# 4_classyTKL_EC_analog.net
KiCad netlist of a schematic drawn in Altium Designer
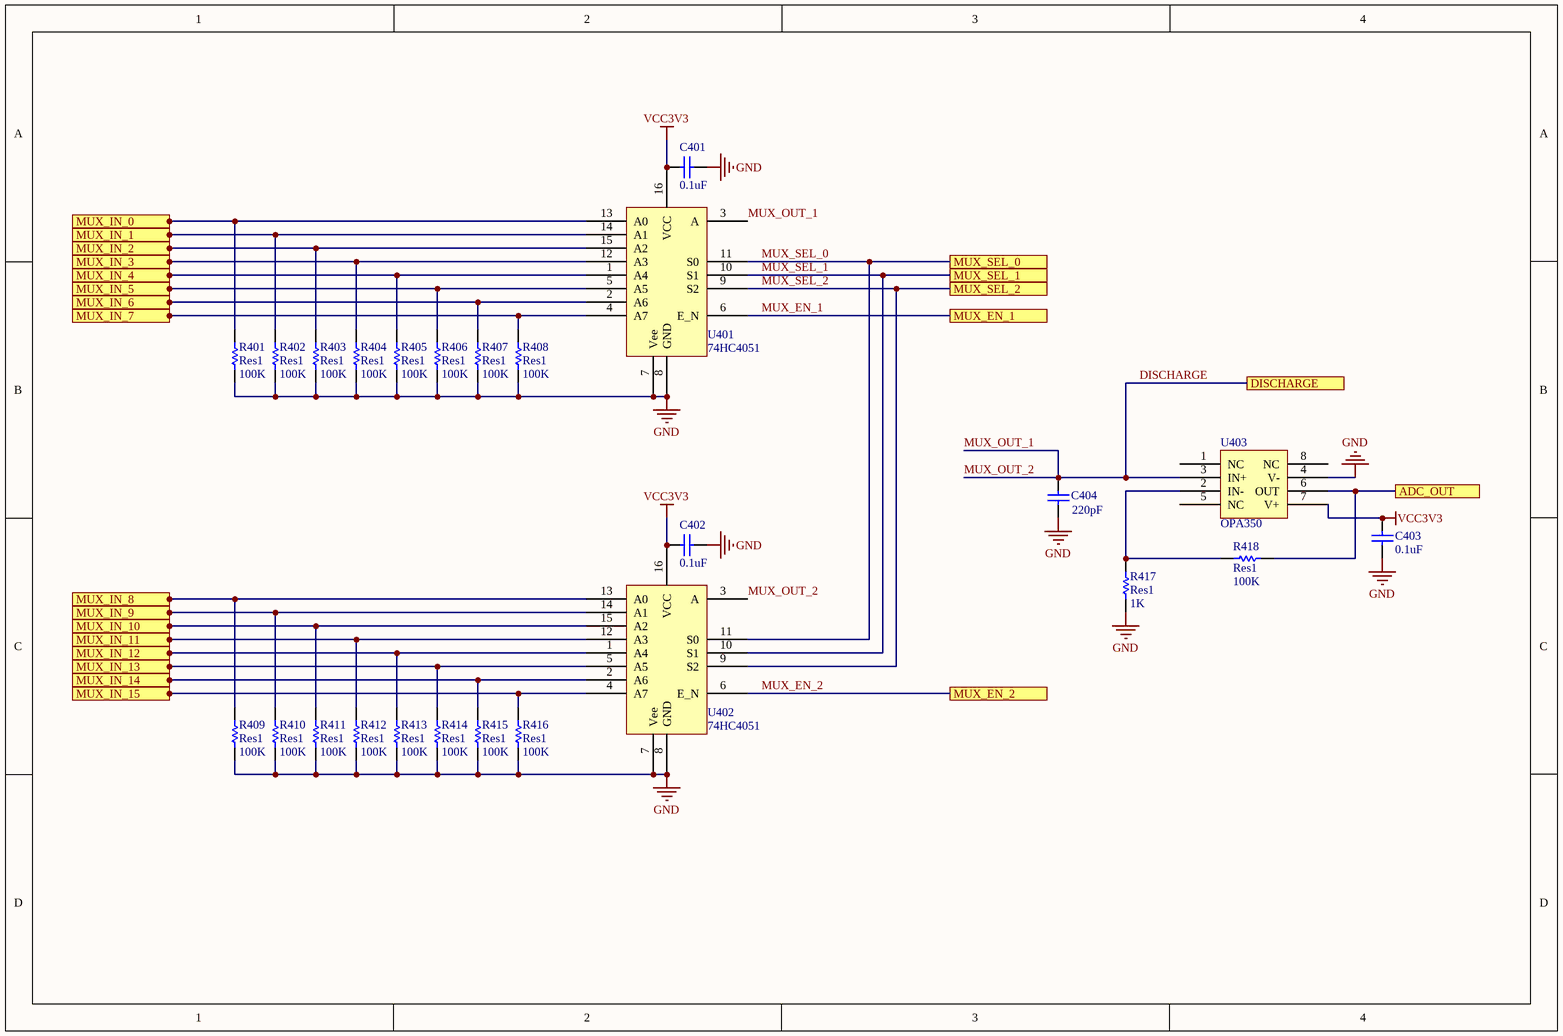
[diagram p0: 4_classyTKL_EC_analog.SchDoc]

(export (version "E")
  (design (tool "Eeschema 10.0.6"))
  (components
    (comp (ref "C401")
      (value "0.1uF")
      (footprint "C0603[1608]")
      (description "Capacitor")
      (fields (field (name "LCSC PART #") "C14663") (field (name "MRF.PART") "CC0603KRX7R9BB104"))
      (libsource (lib "Miscellaneous Devices") (part "Cap"))
    )
    (comp (ref "C402")
      (value "0.1uF")
      (footprint "C0603[1608]")
      (description "Capacitor")
      (fields (field (name "LCSC PART #") "C14663") (field (name "MRF.PART") "CC0603KRX7R9BB104"))
      (libsource (lib "Miscellaneous Devices") (part "Cap"))
    )
    (comp (ref "C403")
      (value "0.1uF")
      (footprint "C0603[1608]")
      (description "Capacitor")
      (fields (field (name "LCSC PART #") "C14663") (field (name "MRF.PART") "CC0603KRX7R9BB104"))
      (libsource (lib "Miscellaneous Devices") (part "Cap"))
    )
    (comp (ref "C404")
      (value "220pF")
      (footprint "C0603[1608]")
      (description "Capacitor")
      (fields (field (name "LCSC PART #") "C1603") (field (name "MRF.PART") "CL10B221KB8NNNC"))
      (libsource (lib "Miscellaneous Devices") (part "Cap"))
    )
    (comp (ref "R401")
      (value "Res1")
      (footprint "R0603[1608]")
      (description "Resistor")
      (fields
        (field (name "ALTIUM_VALUE") "100K")
        (field (name "LCSC PART #") "C25803")
        (field (name "MRF.PART") "0603WAF1003T5E")
      )
      (libsource (lib "Miscellaneous Devices") (part "Res1"))
    )
    (comp (ref "R402")
      (value "Res1")
      (footprint "R0603[1608]")
      (description "Resistor")
      (fields
        (field (name "ALTIUM_VALUE") "100K")
        (field (name "LCSC PART #") "C25803")
        (field (name "MRF.PART") "0603WAF1003T5E")
      )
      (libsource (lib "Miscellaneous Devices") (part "Res1"))
    )
    (comp (ref "R403")
      (value "Res1")
      (footprint "R0603[1608]")
      (description "Resistor")
      (fields
        (field (name "ALTIUM_VALUE") "100K")
        (field (name "LCSC PART #") "C25803")
        (field (name "MRF.PART") "0603WAF1003T5E")
      )
      (libsource (lib "Miscellaneous Devices") (part "Res1"))
    )
    (comp (ref "R404")
      (value "Res1")
      (footprint "R0603[1608]")
      (description "Resistor")
      (fields
        (field (name "ALTIUM_VALUE") "100K")
        (field (name "LCSC PART #") "C25803")
        (field (name "MRF.PART") "0603WAF1003T5E")
      )
      (libsource (lib "Miscellaneous Devices") (part "Res1"))
    )
    (comp (ref "R405")
      (value "Res1")
      (footprint "R0603[1608]")
      (description "Resistor")
      (fields
        (field (name "ALTIUM_VALUE") "100K")
        (field (name "LCSC PART #") "C25803")
        (field (name "MRF.PART") "0603WAF1003T5E")
      )
      (libsource (lib "Miscellaneous Devices") (part "Res1"))
    )
    (comp (ref "R406")
      (value "Res1")
      (footprint "R0603[1608]")
      (description "Resistor")
      (fields
        (field (name "ALTIUM_VALUE") "100K")
        (field (name "LCSC PART #") "C25803")
        (field (name "MRF.PART") "0603WAF1003T5E")
      )
      (libsource (lib "Miscellaneous Devices") (part "Res1"))
    )
    (comp (ref "R407")
      (value "Res1")
      (footprint "R0603[1608]")
      (description "Resistor")
      (fields
        (field (name "ALTIUM_VALUE") "100K")
        (field (name "LCSC PART #") "C25803")
        (field (name "MRF.PART") "0603WAF1003T5E")
      )
      (libsource (lib "Miscellaneous Devices") (part "Res1"))
    )
    (comp (ref "R408")
      (value "Res1")
      (footprint "R0603[1608]")
      (description "Resistor")
      (fields
        (field (name "ALTIUM_VALUE") "100K")
        (field (name "LCSC PART #") "C25803")
        (field (name "MRF.PART") "0603WAF1003T5E")
      )
      (libsource (lib "Miscellaneous Devices") (part "Res1"))
    )
    (comp (ref "R409")
      (value "Res1")
      (footprint "R0603[1608]")
      (description "Resistor")
      (fields
        (field (name "ALTIUM_VALUE") "100K")
        (field (name "LCSC PART #") "C25803")
        (field (name "MRF.PART") "0603WAF1003T5E")
      )
      (libsource (lib "Miscellaneous Devices") (part "Res1"))
    )
    (comp (ref "R410")
      (value "Res1")
      (footprint "R0603[1608]")
      (description "Resistor")
      (fields
        (field (name "ALTIUM_VALUE") "100K")
        (field (name "LCSC PART #") "C25803")
        (field (name "MRF.PART") "0603WAF1003T5E")
      )
      (libsource (lib "Miscellaneous Devices") (part "Res1"))
    )
    (comp (ref "R411")
      (value "Res1")
      (footprint "R0603[1608]")
      (description "Resistor")
      (fields
        (field (name "ALTIUM_VALUE") "100K")
        (field (name "LCSC PART #") "C25803")
        (field (name "MRF.PART") "0603WAF1003T5E")
      )
      (libsource (lib "Miscellaneous Devices") (part "Res1"))
    )
    (comp (ref "R412")
      (value "Res1")
      (footprint "R0603[1608]")
      (description "Resistor")
      (fields
        (field (name "ALTIUM_VALUE") "100K")
        (field (name "LCSC PART #") "C25803")
        (field (name "MRF.PART") "0603WAF1003T5E")
      )
      (libsource (lib "Miscellaneous Devices") (part "Res1"))
    )
    (comp (ref "R413")
      (value "Res1")
      (footprint "R0603[1608]")
      (description "Resistor")
      (fields
        (field (name "ALTIUM_VALUE") "100K")
        (field (name "LCSC PART #") "C25803")
        (field (name "MRF.PART") "0603WAF1003T5E")
      )
      (libsource (lib "Miscellaneous Devices") (part "Res1"))
    )
    (comp (ref "R414")
      (value "Res1")
      (footprint "R0603[1608]")
      (description "Resistor")
      (fields
        (field (name "ALTIUM_VALUE") "100K")
        (field (name "LCSC PART #") "C25803")
        (field (name "MRF.PART") "0603WAF1003T5E")
      )
      (libsource (lib "Miscellaneous Devices") (part "Res1"))
    )
    (comp (ref "R415")
      (value "Res1")
      (footprint "R0603[1608]")
      (description "Resistor")
      (fields
        (field (name "ALTIUM_VALUE") "100K")
        (field (name "LCSC PART #") "C25803")
        (field (name "MRF.PART") "0603WAF1003T5E")
      )
      (libsource (lib "Miscellaneous Devices") (part "Res1"))
    )
    (comp (ref "R416")
      (value "Res1")
      (footprint "R0603[1608]")
      (description "Resistor")
      (fields
        (field (name "ALTIUM_VALUE") "100K")
        (field (name "LCSC PART #") "C25803")
        (field (name "MRF.PART") "0603WAF1003T5E")
      )
      (libsource (lib "Miscellaneous Devices") (part "Res1"))
    )
    (comp (ref "R417")
      (value "Res1")
      (footprint "R0603[1608]")
      (description "Resistor")
      (fields
        (field (name "ALTIUM_VALUE") "1K")
        (field (name "LCSC PART #") "C21190")
        (field (name "MRF.PART") "0603WAF1001T5E")
      )
      (libsource (lib "Miscellaneous Devices") (part "Res1"))
    )
    (comp (ref "R418")
      (value "Res1")
      (footprint "R0603[1608]")
      (description "Resistor")
      (fields
        (field (name "ALTIUM_VALUE") "100K")
        (field (name "LCSC PART #") "C25803")
        (field (name "MRF.PART") "0603WAF1003T5E")
      )
      (libsource (lib "Miscellaneous Devices") (part "Res1"))
    )
    (comp (ref "U401")
      (value "74HC4051")
      (footprint "Texas_Instruments_D_SOIC16")
      (fields (field (name "LCSC PART #") "C9386") (field (name "MRF.PART") "74HC4051D,653"))
      (libsource (lib "Keebs") (part "74HC4051"))
    )
    (comp (ref "U402")
      (value "74HC4051")
      (footprint "Texas_Instruments_D_SOIC16")
      (fields (field (name "LCSC PART #") "C9386") (field (name "MRF.PART") "74HC4051D,653"))
      (libsource (lib "Keebs") (part "74HC4051"))
    )
    (comp (ref "U403")
      (value "OPA350")
      (footprint "SOIC-8")
      (fields (field (name "LCSC PART #") "C13388") (field (name "MRF.PART") "OPA350UA/2K5"))
      (libsource (lib "Keebs") (part "OPA350"))
    )
  )
  (nets
    (net (code "1") (name "/ADC_OUT") (class "Default")
      (node (ref "R418") (pin "2") (pinfunction "2_2") (pintype "passive"))
      (node (ref "U403") (pin "6") (pinfunction "OUT_6") (pintype "passive"))
    )
    (net (code "2") (name "/DISCHARGE") (class "Default")
      (node (ref "C404") (pin "2") (pinfunction "2_2") (pintype "passive"))
      (node (ref "U401") (pin "3") (pinfunction "A_3") (pintype "passive"))
      (node (ref "U402") (pin "3") (pinfunction "A_3") (pintype "passive"))
      (node (ref "U403") (pin "3") (pinfunction "IN+_3") (pintype "passive"))
    )
    (net (code "3") (name "/MUX_EN_1") (class "Default")
      (node (ref "U401") (pin "6") (pinfunction "E_N_6") (pintype "passive"))
    )
    (net (code "4") (name "/MUX_EN_2") (class "Default")
      (node (ref "U402") (pin "6") (pinfunction "E_N_6") (pintype "passive"))
    )
    (net (code "5") (name "/MUX_IN_0") (class "Default")
      (node (ref "R401") (pin "1") (pinfunction "1_1") (pintype "passive"))
      (node (ref "U401") (pin "13") (pinfunction "A0_13") (pintype "passive"))
    )
    (net (code "6") (name "/MUX_IN_1") (class "Default")
      (node (ref "R402") (pin "1") (pinfunction "1_1") (pintype "passive"))
      (node (ref "U401") (pin "14") (pinfunction "A1_14") (pintype "passive"))
    )
    (net (code "7") (name "/MUX_IN_2") (class "Default")
      (node (ref "R403") (pin "1") (pinfunction "1_1") (pintype "passive"))
      (node (ref "U401") (pin "15") (pinfunction "A2_15") (pintype "passive"))
    )
    (net (code "8") (name "/MUX_IN_3") (class "Default")
      (node (ref "R404") (pin "1") (pinfunction "1_1") (pintype "passive"))
      (node (ref "U401") (pin "12") (pinfunction "A3_12") (pintype "passive"))
    )
    (net (code "9") (name "/MUX_IN_4") (class "Default")
      (node (ref "R405") (pin "1") (pinfunction "1_1") (pintype "passive"))
      (node (ref "U401") (pin "1") (pinfunction "A4_1") (pintype "passive"))
    )
    (net (code "10") (name "/MUX_IN_5") (class "Default")
      (node (ref "R406") (pin "1") (pinfunction "1_1") (pintype "passive"))
      (node (ref "U401") (pin "5") (pinfunction "A5_5") (pintype "passive"))
    )
    (net (code "11") (name "/MUX_IN_6") (class "Default")
      (node (ref "R407") (pin "1") (pinfunction "1_1") (pintype "passive"))
      (node (ref "U401") (pin "2") (pinfunction "A6_2") (pintype "passive"))
    )
    (net (code "12") (name "/MUX_IN_7") (class "Default")
      (node (ref "R408") (pin "1") (pinfunction "1_1") (pintype "passive"))
      (node (ref "U401") (pin "4") (pinfunction "A7_4") (pintype "passive"))
    )
    (net (code "13") (name "/MUX_IN_8") (class "Default")
      (node (ref "R409") (pin "1") (pinfunction "1_1") (pintype "passive"))
      (node (ref "U402") (pin "13") (pinfunction "A0_13") (pintype "passive"))
    )
    (net (code "14") (name "/MUX_IN_9") (class "Default")
      (node (ref "R410") (pin "1") (pinfunction "1_1") (pintype "passive"))
      (node (ref "U402") (pin "14") (pinfunction "A1_14") (pintype "passive"))
    )
    (net (code "15") (name "/MUX_IN_10") (class "Default")
      (node (ref "R411") (pin "1") (pinfunction "1_1") (pintype "passive"))
      (node (ref "U402") (pin "15") (pinfunction "A2_15") (pintype "passive"))
    )
    (net (code "16") (name "/MUX_IN_11") (class "Default")
      (node (ref "R412") (pin "1") (pinfunction "1_1") (pintype "passive"))
      (node (ref "U402") (pin "12") (pinfunction "A3_12") (pintype "passive"))
    )
    (net (code "17") (name "/MUX_IN_12") (class "Default")
      (node (ref "R413") (pin "1") (pinfunction "1_1") (pintype "passive"))
      (node (ref "U402") (pin "1") (pinfunction "A4_1") (pintype "passive"))
    )
    (net (code "18") (name "/MUX_IN_13") (class "Default")
      (node (ref "R414") (pin "1") (pinfunction "1_1") (pintype "passive"))
      (node (ref "U402") (pin "5") (pinfunction "A5_5") (pintype "passive"))
    )
    (net (code "19") (name "/MUX_IN_14") (class "Default")
      (node (ref "R415") (pin "1") (pinfunction "1_1") (pintype "passive"))
      (node (ref "U402") (pin "2") (pinfunction "A6_2") (pintype "passive"))
    )
    (net (code "20") (name "/MUX_IN_15") (class "Default")
      (node (ref "R416") (pin "1") (pinfunction "1_1") (pintype "passive"))
      (node (ref "U402") (pin "4") (pinfunction "A7_4") (pintype "passive"))
    )
    (net (code "21") (name "/MUX_SEL_0") (class "Default")
      (node (ref "U401") (pin "11") (pinfunction "S0_11") (pintype "passive"))
      (node (ref "U402") (pin "11") (pinfunction "S0_11") (pintype "passive"))
    )
    (net (code "22") (name "/MUX_SEL_1") (class "Default")
      (node (ref "U401") (pin "10") (pinfunction "S1_10") (pintype "passive"))
      (node (ref "U402") (pin "10") (pinfunction "S1_10") (pintype "passive"))
    )
    (net (code "23") (name "/MUX_SEL_2") (class "Default")
      (node (ref "U401") (pin "9") (pinfunction "S2_9") (pintype "passive"))
      (node (ref "U402") (pin "9") (pinfunction "S2_9") (pintype "passive"))
    )
    (net (code "24") (name "GND") (class "Default")
      (node (ref "C401") (pin "1") (pinfunction "1_1") (pintype "passive"))
      (node (ref "C402") (pin "1") (pinfunction "1_1") (pintype "passive"))
      (node (ref "C403") (pin "2") (pinfunction "2_2") (pintype "passive"))
      (node (ref "C404") (pin "1") (pinfunction "1_1") (pintype "passive"))
      (node (ref "R401") (pin "2") (pinfunction "2_2") (pintype "passive"))
      (node (ref "R402") (pin "2") (pinfunction "2_2") (pintype "passive"))
      (node (ref "R403") (pin "2") (pinfunction "2_2") (pintype "passive"))
      (node (ref "R404") (pin "2") (pinfunction "2_2") (pintype "passive"))
      (node (ref "R405") (pin "2") (pinfunction "2_2") (pintype "passive"))
      (node (ref "R406") (pin "2") (pinfunction "2_2") (pintype "passive"))
      (node (ref "R407") (pin "2") (pinfunction "2_2") (pintype "passive"))
      (node (ref "R408") (pin "2") (pinfunction "2_2") (pintype "passive"))
      (node (ref "R409") (pin "2") (pinfunction "2_2") (pintype "passive"))
      (node (ref "R410") (pin "2") (pinfunction "2_2") (pintype "passive"))
      (node (ref "R411") (pin "2") (pinfunction "2_2") (pintype "passive"))
      (node (ref "R412") (pin "2") (pinfunction "2_2") (pintype "passive"))
      (node (ref "R413") (pin "2") (pinfunction "2_2") (pintype "passive"))
      (node (ref "R414") (pin "2") (pinfunction "2_2") (pintype "passive"))
      (node (ref "R415") (pin "2") (pinfunction "2_2") (pintype "passive"))
      (node (ref "R416") (pin "2") (pinfunction "2_2") (pintype "passive"))
      (node (ref "R417") (pin "2") (pinfunction "2_2") (pintype "passive"))
      (node (ref "U401") (pin "7") (pinfunction "Vee_7") (pintype "passive"))
      (node (ref "U401") (pin "8") (pinfunction "GND_8") (pintype "passive"))
      (node (ref "U402") (pin "7") (pinfunction "Vee_7") (pintype "passive"))
      (node (ref "U402") (pin "8") (pinfunction "GND_8") (pintype "passive"))
      (node (ref "U403") (pin "4") (pinfunction "V-_4") (pintype "passive"))
    )
    (net (code "25") (name "Net-(U403-IN-)") (class "Default")
      (node (ref "R417") (pin "1") (pinfunction "1_1") (pintype "passive"))
      (node (ref "R418") (pin "1") (pinfunction "1_1") (pintype "passive"))
      (node (ref "U403") (pin "2") (pinfunction "IN-_2") (pintype "passive"))
    )
    (net (code "26") (name "VCC3V3") (class "Default")
      (node (ref "C401") (pin "2") (pinfunction "2_2") (pintype "passive"))
      (node (ref "C402") (pin "2") (pinfunction "2_2") (pintype "passive"))
      (node (ref "C403") (pin "1") (pinfunction "1_1") (pintype "passive"))
      (node (ref "U401") (pin "16") (pinfunction "VCC_16") (pintype "passive"))
      (node (ref "U402") (pin "16") (pinfunction "VCC_16") (pintype "passive"))
      (node (ref "U403") (pin "7") (pinfunction "V+_7") (pintype "passive"))
    )
    (net (code "27") (name "unconnected-(U403-NC-Pad1)") (class "Default")
      (node (ref "U403") (pin "1") (pinfunction "NC_1") (pintype "passive"))
    )
    (net (code "28") (name "unconnected-(U403-NC-Pad5)") (class "Default")
      (node (ref "U403") (pin "5") (pinfunction "NC_5") (pintype "passive"))
    )
    (net (code "29") (name "unconnected-(U403-NC-Pad8)") (class "Default")
      (node (ref "U403") (pin "8") (pinfunction "NC_8") (pintype "passive"))
    )
  )
)
